# Arduino_FTDI_UART.net
KiCad netlist of a schematic drawn in EAGLE
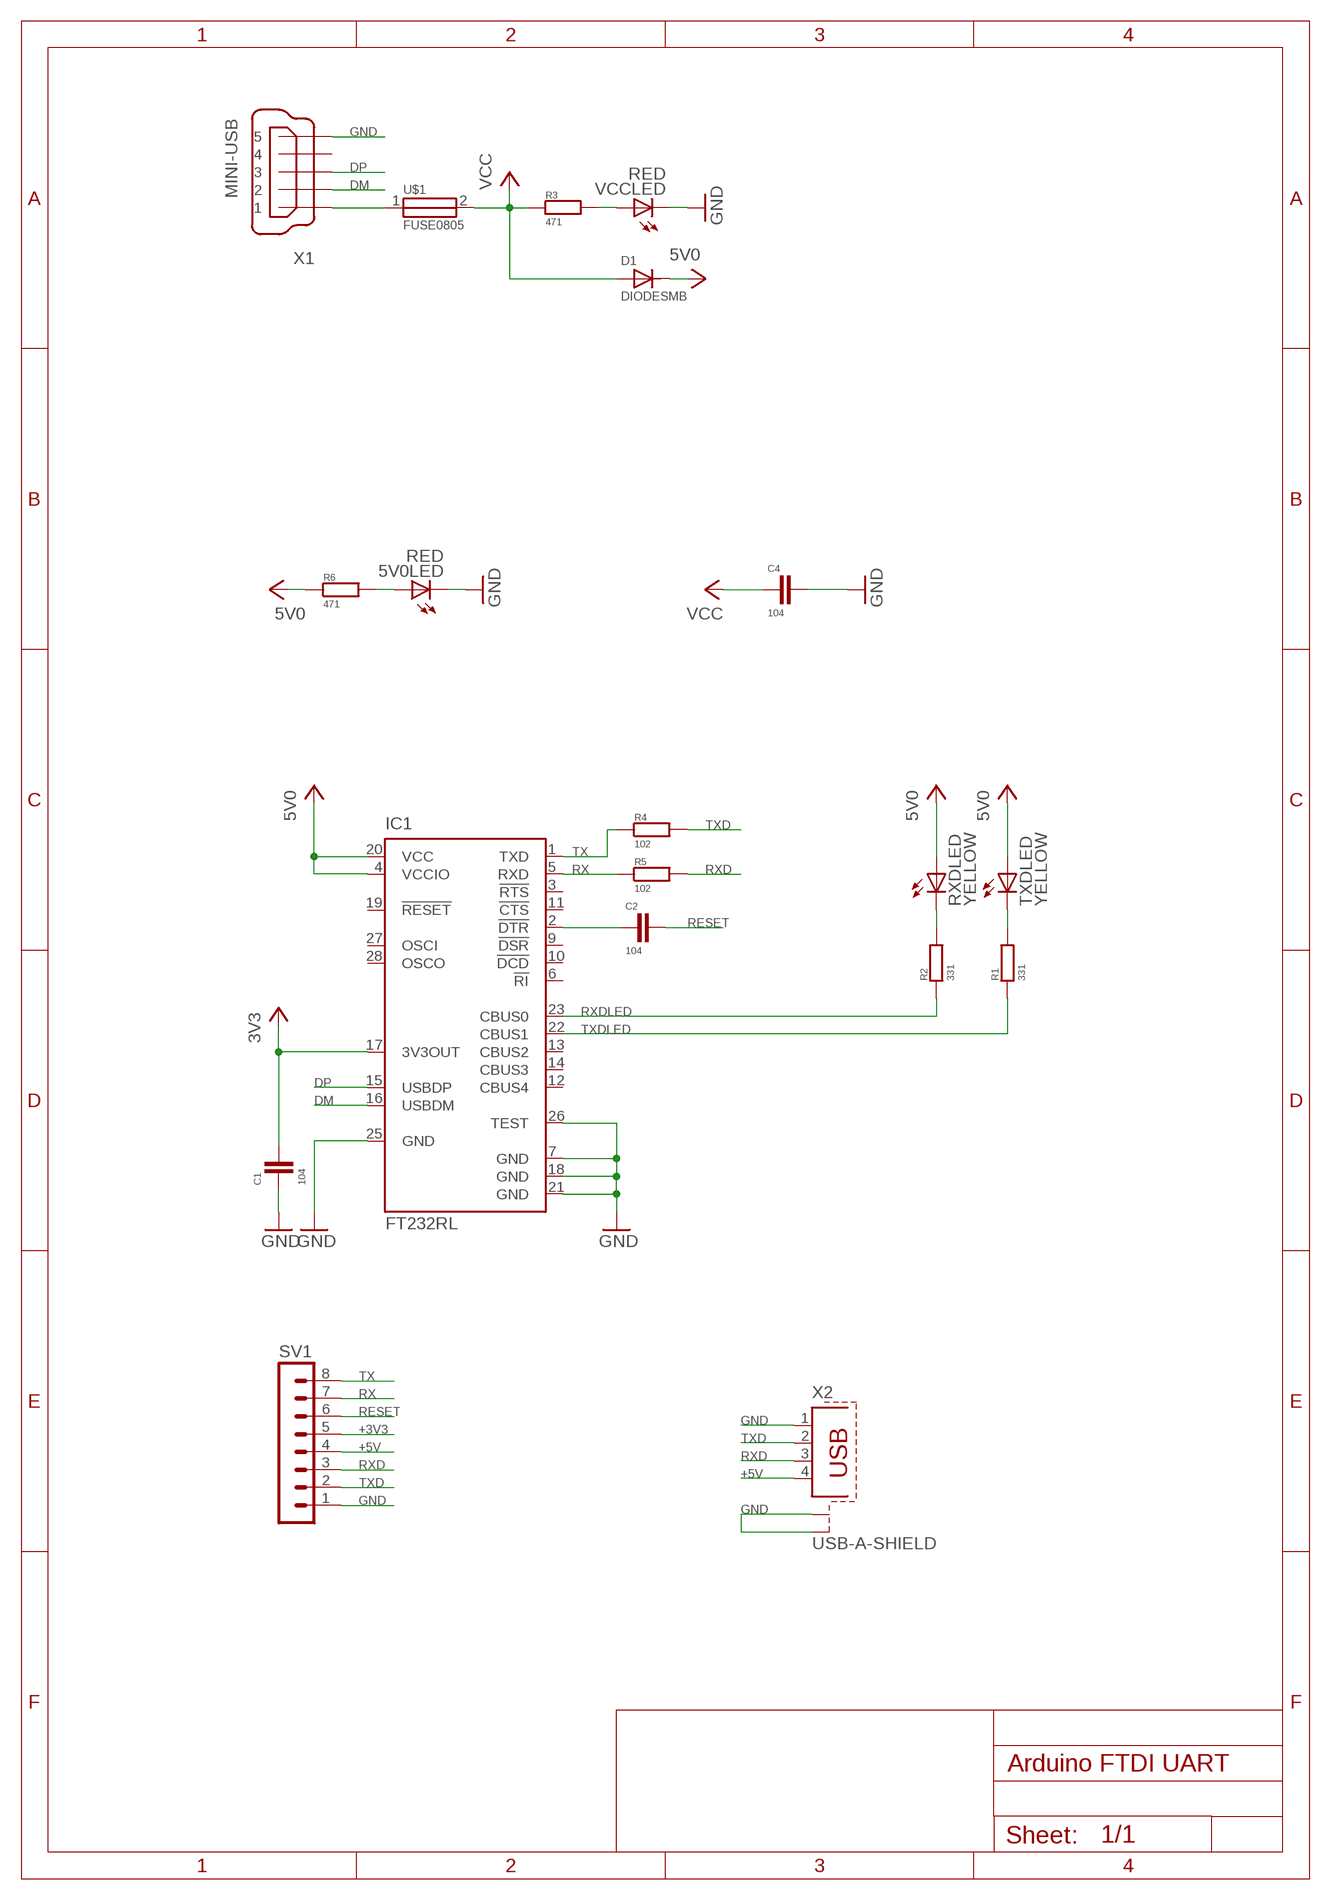
[diagram p0: schematic, sheet 1]

(export (version "E")
  (design (tool "Eeschema 10.0.6"))
  (components
    (comp (ref "5V0LED")
      (value "RED")
      (footprint "eagle-import:CHIPLED_0805")
      (libsource (lib "eagle-import") (part "LEDCHIPLED_0805"))
    )
    (comp (ref "C1")
      (value "104")
      (footprint "eagle-import:C0805")
      (libsource (lib "eagle-import") (part "CC0805"))
    )
    (comp (ref "C2")
      (value "104")
      (footprint "eagle-import:C0805")
      (libsource (lib "eagle-import") (part "CC0805"))
    )
    (comp (ref "C4")
      (value "104")
      (footprint "eagle-import:C0805")
      (libsource (lib "eagle-import") (part "CC0805"))
    )
    (comp (ref "D1")
      (value "DIODESMB")
      (footprint "eagle-import:SMB")
      (libsource (lib "eagle-import") (part "DIODESMB"))
    )
    (comp (ref "IC1")
      (value "FT232RL")
      (footprint "eagle-import:SSOP28")
      (libsource (lib "eagle-import") (part "FT232RL"))
    )
    (comp (ref "R1")
      (value "331")
      (footprint "eagle-import:R0805")
      (libsource (lib "eagle-import") (part "RR0805"))
    )
    (comp (ref "R2")
      (value "331")
      (footprint "eagle-import:R0805")
      (libsource (lib "eagle-import") (part "RR0805"))
    )
    (comp (ref "R3")
      (value "471")
      (footprint "eagle-import:R0805")
      (libsource (lib "eagle-import") (part "RR0805"))
    )
    (comp (ref "R4")
      (value "102")
      (footprint "eagle-import:R0805")
      (libsource (lib "eagle-import") (part "RR0805"))
    )
    (comp (ref "R5")
      (value "102")
      (footprint "eagle-import:R0805")
      (libsource (lib "eagle-import") (part "RR0805"))
    )
    (comp (ref "R6")
      (value "471")
      (footprint "eagle-import:R0805")
      (libsource (lib "eagle-import") (part "RR0805"))
    )
    (comp (ref "RXDLED")
      (value "YELLOW")
      (footprint "eagle-import:CHIPLED_0805")
      (libsource (lib "eagle-import") (part "LEDCHIPLED_0805"))
    )
    (comp (ref "SV1")
      (value "MA08-1")
      (footprint "eagle-import:MA08-1")
      (libsource (lib "eagle-import") (part "MA08-1"))
    )
    (comp (ref "TXDLED")
      (value "YELLOW")
      (footprint "eagle-import:CHIPLED_0805")
      (libsource (lib "eagle-import") (part "LEDCHIPLED_0805"))
    )
    (comp (ref "U$1")
      (value "FUSE0805")
      (footprint "eagle-import:F0805")
      (libsource (lib "eagle-import") (part "FUSE0805"))
    )
    (comp (ref "VCCLED")
      (value "RED")
      (footprint "eagle-import:CHIPLED_0805")
      (libsource (lib "eagle-import") (part "LEDCHIPLED_0805"))
    )
    (comp (ref "X1")
      (value "MINI-USB")
      (footprint "eagle-import:32005-201")
      (libsource (lib "eagle-import") (part "MINI-USB-32005-201"))
    )
    (comp (ref "X2")
      (value "USB-A-SHIELD")
      (footprint "eagle-import:USB-A-SHIELD")
      (libsource (lib "eagle-import") (part "USB-A-SHIELD"))
    )
  )
  (nets
    (net (code "1") (name "/DM") (class "Default")
      (node (ref "IC1") (pin "16") (pinfunction "USBDM_16") (pintype "bidirectional"))
      (node (ref "X1") (pin "2") (pinfunction "2_2") (pintype "passive"))
    )
    (net (code "2") (name "/DP") (class "Default")
      (node (ref "IC1") (pin "15") (pinfunction "USBDP_15") (pintype "bidirectional"))
      (node (ref "X1") (pin "3") (pinfunction "3_3") (pintype "passive"))
    )
    (net (code "3") (name "/RESET") (class "Default")
      (node (ref "C2") (pin "1") (pinfunction "1_1") (pintype "bidirectional"))
      (node (ref "SV1") (pin "6") (pinfunction "6_6") (pintype "passive"))
    )
    (net (code "4") (name "/RX") (class "Default")
      (node (ref "IC1") (pin "5") (pinfunction "RXD_5") (pintype "input"))
      (node (ref "R5") (pin "1") (pinfunction "1_1") (pintype "bidirectional"))
      (node (ref "SV1") (pin "7") (pinfunction "7_7") (pintype "passive"))
    )
    (net (code "5") (name "/RXD") (class "Default")
      (node (ref "R5") (pin "2") (pinfunction "2_2") (pintype "bidirectional"))
      (node (ref "SV1") (pin "3") (pinfunction "3_3") (pintype "passive"))
      (node (ref "X2") (pin "3") (pinfunction "3_3") (pintype "passive"))
    )
    (net (code "6") (name "/RXDLED") (class "Default")
      (node (ref "IC1") (pin "23") (pinfunction "CBUS0_23") (pintype "bidirectional"))
      (node (ref "R2") (pin "1") (pinfunction "1_1") (pintype "bidirectional"))
    )
    (net (code "7") (name "/TX") (class "Default")
      (node (ref "IC1") (pin "1") (pinfunction "TXD_1") (pintype "output"))
      (node (ref "R4") (pin "1") (pinfunction "1_1") (pintype "bidirectional"))
      (node (ref "SV1") (pin "8") (pinfunction "8_8") (pintype "passive"))
    )
    (net (code "8") (name "/TXD") (class "Default")
      (node (ref "R4") (pin "2") (pinfunction "2_2") (pintype "bidirectional"))
      (node (ref "SV1") (pin "2") (pinfunction "2_2") (pintype "passive"))
      (node (ref "X2") (pin "2") (pinfunction "2_2") (pintype "passive"))
    )
    (net (code "9") (name "/TXDLED") (class "Default")
      (node (ref "IC1") (pin "22") (pinfunction "CBUS1_22") (pintype "bidirectional"))
      (node (ref "R1") (pin "1") (pinfunction "1_1") (pintype "bidirectional"))
    )
    (net (code "10") (name "3V3") (class "Default")
      (node (ref "C1") (pin "1") (pinfunction "1_1") (pintype "bidirectional"))
      (node (ref "IC1") (pin "17") (pinfunction "3V3OUT_17") (pintype "output"))
      (node (ref "SV1") (pin "5") (pinfunction "5_5") (pintype "passive"))
    )
    (net (code "11") (name "5V0") (class "Default")
      (node (ref "D1") (pin "1") (pinfunction "1_1") (pintype "bidirectional"))
      (node (ref "IC1") (pin "20") (pinfunction "VCC_20") (pintype "power_in"))
      (node (ref "IC1") (pin "4") (pinfunction "VCCIO_4") (pintype "power_in"))
      (node (ref "R6") (pin "1") (pinfunction "1_1") (pintype "bidirectional"))
      (node (ref "RXDLED") (pin "A") (pinfunction "A_A") (pintype "passive"))
      (node (ref "SV1") (pin "4") (pinfunction "4_4") (pintype "passive"))
      (node (ref "TXDLED") (pin "A") (pinfunction "A_A") (pintype "passive"))
      (node (ref "X2") (pin "4") (pinfunction "4_4") (pintype "passive"))
    )
    (net (code "12") (name "GND") (class "Default")
      (node (ref "5V0LED") (pin "C") (pinfunction "C_C") (pintype "passive"))
      (node (ref "C1") (pin "2") (pinfunction "2_2") (pintype "bidirectional"))
      (node (ref "C4") (pin "1") (pinfunction "1_1") (pintype "bidirectional"))
      (node (ref "IC1") (pin "18") (pinfunction "GND_18") (pintype "power_in"))
      (node (ref "IC1") (pin "21") (pinfunction "GND_21") (pintype "power_in"))
      (node (ref "IC1") (pin "25") (pinfunction "GND_25") (pintype "power_in"))
      (node (ref "IC1") (pin "26") (pinfunction "TEST_26") (pintype "input"))
      (node (ref "IC1") (pin "7") (pinfunction "GND_7") (pintype "power_in"))
      (node (ref "SV1") (pin "1") (pinfunction "1_1") (pintype "passive"))
      (node (ref "VCCLED") (pin "C") (pinfunction "C_C") (pintype "passive"))
      (node (ref "X1") (pin "5") (pinfunction "5_5") (pintype "passive"))
      (node (ref "X2") (pin "1") (pinfunction "1_1") (pintype "passive"))
      (node (ref "X2") (pin "S1") (pinfunction "S1_S1") (pintype "passive"))
      (node (ref "X2") (pin "S2") (pinfunction "S2_S2") (pintype "passive"))
    )
    (net (code "13") (name "Net-(5V0LED-PadA)") (class "Default")
      (node (ref "5V0LED") (pin "A") (pinfunction "A_A") (pintype "passive"))
      (node (ref "R6") (pin "2") (pinfunction "2_2") (pintype "bidirectional"))
    )
    (net (code "14") (name "Net-(IC1-~{DTR})") (class "Default")
      (node (ref "C2") (pin "2") (pinfunction "2_2") (pintype "bidirectional"))
      (node (ref "IC1") (pin "2") (pinfunction "~{DTR}_2") (pintype "output"))
    )
    (net (code "15") (name "Net-(R1-Pad2)") (class "Default")
      (node (ref "R1") (pin "2") (pinfunction "2_2") (pintype "bidirectional"))
      (node (ref "TXDLED") (pin "C") (pinfunction "C_C") (pintype "passive"))
    )
    (net (code "16") (name "Net-(R2-Pad2)") (class "Default")
      (node (ref "R2") (pin "2") (pinfunction "2_2") (pintype "bidirectional"))
      (node (ref "RXDLED") (pin "C") (pinfunction "C_C") (pintype "passive"))
    )
    (net (code "17") (name "Net-(R3-Pad2)") (class "Default")
      (node (ref "R3") (pin "2") (pinfunction "2_2") (pintype "bidirectional"))
      (node (ref "VCCLED") (pin "A") (pinfunction "A_A") (pintype "passive"))
    )
    (net (code "18") (name "Net-(U$1-P$1)") (class "Default")
      (node (ref "U$1") (pin "1") (pinfunction "P$1_1") (pintype "bidirectional"))
      (node (ref "X1") (pin "1") (pinfunction "1_1") (pintype "passive"))
    )
    (net (code "19") (name "VCC") (class "Default")
      (node (ref "C4") (pin "2") (pinfunction "2_2") (pintype "bidirectional"))
      (node (ref "D1") (pin "2") (pinfunction "2_2") (pintype "bidirectional"))
      (node (ref "R3") (pin "1") (pinfunction "1_1") (pintype "bidirectional"))
      (node (ref "U$1") (pin "2") (pinfunction "P$2_2") (pintype "bidirectional"))
    )
    (net (code "20") (name "unconnected-(IC1-CBUS2-Pad13)") (class "Default")
      (node (ref "IC1") (pin "13") (pinfunction "CBUS2_13") (pintype "bidirectional"))
    )
    (net (code "21") (name "unconnected-(IC1-CBUS3-Pad14)") (class "Default")
      (node (ref "IC1") (pin "14") (pinfunction "CBUS3_14") (pintype "bidirectional"))
    )
    (net (code "22") (name "unconnected-(IC1-CBUS4-Pad12)") (class "Default")
      (node (ref "IC1") (pin "12") (pinfunction "CBUS4_12") (pintype "bidirectional"))
    )
    (net (code "23") (name "unconnected-(IC1-OSCI-Pad27)") (class "Default")
      (node (ref "IC1") (pin "27") (pinfunction "OSCI_27") (pintype "input"))
    )
    (net (code "24") (name "unconnected-(IC1-OSCO-Pad28)") (class "Default")
      (node (ref "IC1") (pin "28") (pinfunction "OSCO_28") (pintype "output"))
    )
    (net (code "25") (name "unconnected-(IC1-~{CTS}-Pad11)") (class "Default")
      (node (ref "IC1") (pin "11") (pinfunction "~{CTS}_11") (pintype "input"))
    )
    (net (code "26") (name "unconnected-(IC1-~{DCD}-Pad10)") (class "Default")
      (node (ref "IC1") (pin "10") (pinfunction "~{DCD}_10") (pintype "input"))
    )
    (net (code "27") (name "unconnected-(IC1-~{DSR}-Pad9)") (class "Default")
      (node (ref "IC1") (pin "9") (pinfunction "~{DSR}_9") (pintype "input"))
    )
    (net (code "28") (name "unconnected-(IC1-~{RESET}-Pad19)") (class "Default")
      (node (ref "IC1") (pin "19") (pinfunction "~{RESET}_19") (pintype "input"))
    )
    (net (code "29") (name "unconnected-(IC1-~{RI}-Pad6)") (class "Default")
      (node (ref "IC1") (pin "6") (pinfunction "~{RI}_6") (pintype "input"))
    )
    (net (code "30") (name "unconnected-(IC1-~{RTS}-Pad3)") (class "Default")
      (node (ref "IC1") (pin "3") (pinfunction "~{RTS}_3") (pintype "output"))
    )
    (net (code "31") (name "unconnected-(X1-Pad4)") (class "Default")
      (node (ref "X1") (pin "4") (pinfunction "4_4") (pintype "passive"))
    )
  )
)
